# schematic.net
KiCad netlist of a schematic drawn in Altium Designer
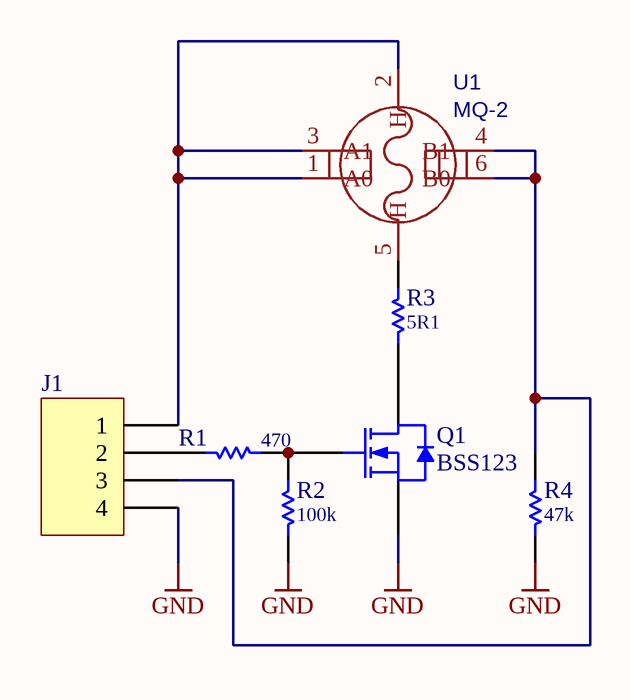
[diagram p0: schematic.SchDoc]

(export (version "E")
  (design (tool "Eeschema 10.0.6"))
  (components
    (comp (ref "J1")
      (value "532610471")
      (footprint "CONN_MOLEX_532610471")
      (libsource (lib "Schlib1") (part "Header 3"))
    )
    (comp (ref "Q1")
      (value "BSS123")
      (footprint "SOT-23")
      (libsource (lib "Miscellaneous Devices") (part "2N7002"))
    )
    (comp (ref "R1")
      (value "470")
      (footprint "R0603")
      (description "470 0603")
      (libsource (lib "Miscellaneous Devices") (part "RES"))
    )
    (comp (ref "R2")
      (value "100k")
      (footprint "R0603")
      (description "100k 0603")
      (libsource (lib "Miscellaneous Devices") (part "RES"))
    )
    (comp (ref "R3")
      (value "5R1")
      (footprint "R1206")
      (description "5R1 1206")
      (libsource (lib "Miscellaneous Devices") (part "RES"))
    )
    (comp (ref "R4")
      (value "47k")
      (footprint "R1206")
      (description "47k 1206")
      (libsource (lib "Miscellaneous Devices") (part "RES"))
    )
    (comp (ref "U1")
      (value "MQ-2")
      (footprint "SENSOR-TH_MQ-2")
      (libsource (lib "altium-import") (part "root_2_mirrored_MQ-2_"))
    )
  )
  (nets
    (net (code "1") (name "GND") (class "Default")
      (node (ref "J1") (pin "4") (pinfunction "4_4") (pintype "passive"))
      (node (ref "Q1") (pin "2") (pinfunction "SOURCE_2") (pintype "passive"))
      (node (ref "R2") (pin "2") (pinfunction "2_2") (pintype "passive"))
      (node (ref "R4") (pin "2") (pinfunction "2_2") (pintype "passive"))
    )
    (net (code "2") (name "Net-(J1-Pad2)") (class "Default")
      (node (ref "J1") (pin "2") (pinfunction "2_2") (pintype "passive"))
      (node (ref "R1") (pin "2") (pinfunction "2_2") (pintype "passive"))
    )
    (net (code "3") (name "Net-(Q1-DRAIN)") (class "Default")
      (node (ref "Q1") (pin "3") (pinfunction "DRAIN_3") (pintype "passive"))
      (node (ref "R3") (pin "2") (pinfunction "2_2") (pintype "passive"))
    )
    (net (code "4") (name "Net-(Q1-GATE)") (class "Default")
      (node (ref "Q1") (pin "1") (pinfunction "GATE_1") (pintype "passive"))
      (node (ref "R1") (pin "1") (pinfunction "1_1") (pintype "passive"))
      (node (ref "R2") (pin "1") (pinfunction "1_1") (pintype "passive"))
    )
    (net (code "5") (name "Net-(R3-Pad1)") (class "Default")
      (node (ref "R3") (pin "1") (pinfunction "1_1") (pintype "passive"))
      (node (ref "U1") (pin "5") (pinfunction "H_5") (pintype "passive"))
    )
    (net (code "6") (name "Net-(U1-A0)") (class "Default")
      (node (ref "J1") (pin "1") (pinfunction "1_1") (pintype "passive"))
      (node (ref "U1") (pin "1") (pinfunction "A0_1") (pintype "passive"))
      (node (ref "U1") (pin "2") (pinfunction "H_2") (pintype "passive"))
      (node (ref "U1") (pin "3") (pinfunction "A1_3") (pintype "passive"))
    )
    (net (code "7") (name "Net-(U1-B0)") (class "Default")
      (node (ref "J1") (pin "3") (pinfunction "3_3") (pintype "passive"))
      (node (ref "R4") (pin "1") (pinfunction "1_1") (pintype "passive"))
      (node (ref "U1") (pin "4") (pinfunction "B1_4") (pintype "passive"))
      (node (ref "U1") (pin "6") (pinfunction "B0_6") (pintype "passive"))
    )
  )
)
